# 7segement4digits1badidea-max7219-smd-mk-.net
KiCad netlist of a schematic drawn in EAGLE
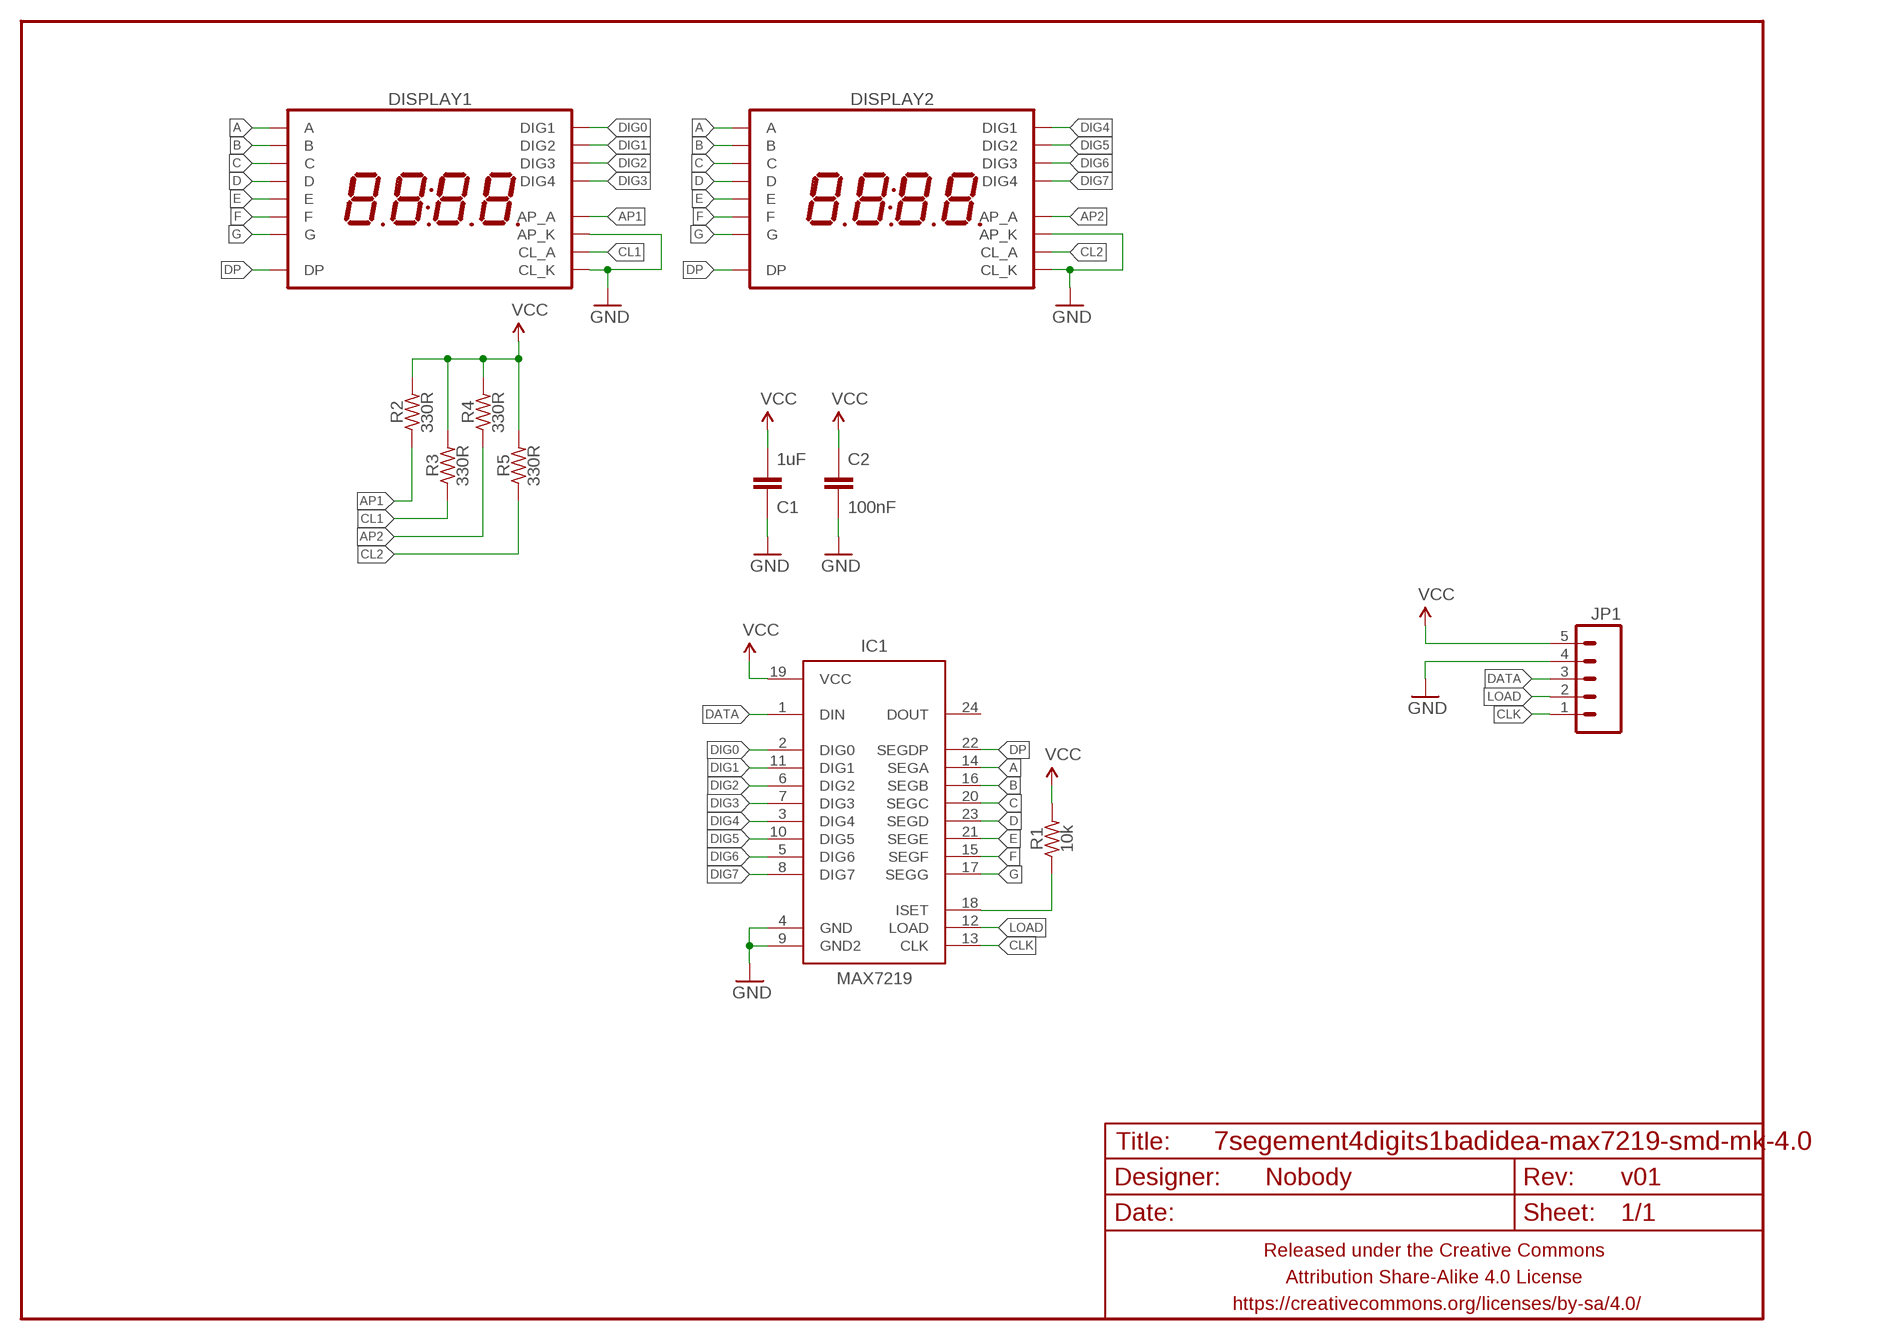
[diagram p0: schematic, sheet 1]

(export (version "E")
  (design (tool "Eeschema 10.0.6"))
  (components
    (comp (ref "C1")
      (value "1uF")
      (footprint "eagle-import:C0805")
      (libsource (lib "eagle-import") (part "CAPACITOR-CERAMICC0805"))
    )
    (comp (ref "C2")
      (value "100nF")
      (footprint "eagle-import:C0805")
      (libsource (lib "eagle-import") (part "CAPACITOR-CERAMICC0805"))
    )
    (comp (ref "DISPLAY1")
      (value "7SEG_4DIGIT_COLON_APOS")
      (footprint "eagle-import:7SEG_4DIG_10MM")
      (libsource (lib "eagle-import") (part "7SEG_4DIGIT_COLON_APOS"))
    )
    (comp (ref "DISPLAY2")
      (value "7SEG_4DIGIT_COLON_APOS")
      (footprint "eagle-import:7SEG_4DIG_10MM")
      (libsource (lib "eagle-import") (part "7SEG_4DIGIT_COLON_APOS"))
    )
    (comp (ref "FRAME1")
      (value "FRAME-LETTERNO_PACKAGE")
      (footprint "eagle-import:DUMMY")
      (fields (field (name "DESIGNER") "Nobody"))
      (libsource (lib "eagle-import") (part "FRAME-LETTERNO_PACKAGE"))
    )
    (comp (ref "IC1")
      (value "MAX7219")
      (footprint "eagle-import:SO24W")
      (libsource (lib "eagle-import") (part "MAX7219SOIC-W"))
    )
    (comp (ref "JP1")
      (value "M05PTH")
      (footprint "eagle-import:1X05")
      (libsource (lib "eagle-import") (part "M05PTH"))
    )
    (comp (ref "R1")
      (value "10k")
      (footprint "eagle-import:R0805")
      (libsource (lib "eagle-import") (part "RESISTORR0805"))
    )
    (comp (ref "R2")
      (value "330R")
      (footprint "eagle-import:R0805")
      (libsource (lib "eagle-import") (part "RESISTORR0805"))
    )
    (comp (ref "R3")
      (value "330R")
      (footprint "eagle-import:R0805")
      (libsource (lib "eagle-import") (part "RESISTORR0805"))
    )
    (comp (ref "R4")
      (value "330R")
      (footprint "eagle-import:R0805")
      (libsource (lib "eagle-import") (part "RESISTORR0805"))
    )
    (comp (ref "R5")
      (value "330R")
      (footprint "eagle-import:R0805")
      (libsource (lib "eagle-import") (part "RESISTORR0805"))
    )
  )
  (nets
    (net (code "1") (name "A") (class "Default")
      (node (ref "DISPLAY1") (pin "14") (pinfunction "A_14") (pintype "passive"))
      (node (ref "DISPLAY2") (pin "14") (pinfunction "A_14") (pintype "passive"))
      (node (ref "IC1") (pin "14") (pinfunction "SEGA_14") (pintype "bidirectional"))
    )
    (net (code "2") (name "AP1") (class "Default")
      (node (ref "DISPLAY1") (pin "10") (pinfunction "AP_A_10") (pintype "bidirectional"))
      (node (ref "R2") (pin "1") (pinfunction "1_1") (pintype "passive"))
    )
    (net (code "3") (name "AP2") (class "Default")
      (node (ref "DISPLAY2") (pin "10") (pinfunction "AP_A_10") (pintype "bidirectional"))
      (node (ref "R4") (pin "1") (pinfunction "1_1") (pintype "passive"))
    )
    (net (code "4") (name "B") (class "Default")
      (node (ref "DISPLAY1") (pin "16") (pinfunction "B_16") (pintype "passive"))
      (node (ref "DISPLAY2") (pin "16") (pinfunction "B_16") (pintype "passive"))
      (node (ref "IC1") (pin "16") (pinfunction "SEGB_16") (pintype "bidirectional"))
    )
    (net (code "5") (name "C") (class "Default")
      (node (ref "DISPLAY1") (pin "13") (pinfunction "C_13") (pintype "passive"))
      (node (ref "DISPLAY2") (pin "13") (pinfunction "C_13") (pintype "passive"))
      (node (ref "IC1") (pin "20") (pinfunction "SEGC_20") (pintype "bidirectional"))
    )
    (net (code "6") (name "CL1") (class "Default")
      (node (ref "DISPLAY1") (pin "4") (pinfunction "CL_A_4") (pintype "passive"))
      (node (ref "R3") (pin "1") (pinfunction "1_1") (pintype "passive"))
    )
    (net (code "7") (name "CL2") (class "Default")
      (node (ref "DISPLAY2") (pin "4") (pinfunction "CL_A_4") (pintype "passive"))
      (node (ref "R5") (pin "1") (pinfunction "1_1") (pintype "passive"))
    )
    (net (code "8") (name "CLK") (class "Default")
      (node (ref "IC1") (pin "13") (pinfunction "CLK_13") (pintype "bidirectional"))
      (node (ref "JP1") (pin "1") (pinfunction "1_1") (pintype "passive"))
    )
    (net (code "9") (name "D") (class "Default")
      (node (ref "DISPLAY1") (pin "3") (pinfunction "D_3") (pintype "passive"))
      (node (ref "DISPLAY2") (pin "3") (pinfunction "D_3") (pintype "passive"))
      (node (ref "IC1") (pin "23") (pinfunction "SEGD_23") (pintype "bidirectional"))
    )
    (net (code "10") (name "DATA") (class "Default")
      (node (ref "IC1") (pin "1") (pinfunction "DIN_1") (pintype "bidirectional"))
      (node (ref "JP1") (pin "3") (pinfunction "3_3") (pintype "passive"))
    )
    (net (code "11") (name "DIG0") (class "Default")
      (node (ref "DISPLAY1") (pin "1") (pinfunction "DIG1_1") (pintype "passive"))
      (node (ref "IC1") (pin "2") (pinfunction "DIG0_2") (pintype "bidirectional"))
    )
    (net (code "12") (name "DIG1") (class "Default")
      (node (ref "DISPLAY1") (pin "2") (pinfunction "DIG2_2") (pintype "passive"))
      (node (ref "IC1") (pin "11") (pinfunction "DIG1_11") (pintype "bidirectional"))
    )
    (net (code "13") (name "DIG2") (class "Default")
      (node (ref "DISPLAY1") (pin "6") (pinfunction "DIG3_6") (pintype "passive"))
      (node (ref "IC1") (pin "6") (pinfunction "DIG2_6") (pintype "bidirectional"))
    )
    (net (code "14") (name "DIG3") (class "Default")
      (node (ref "DISPLAY1") (pin "8") (pinfunction "DIG4_8") (pintype "passive"))
      (node (ref "IC1") (pin "7") (pinfunction "DIG3_7") (pintype "bidirectional"))
    )
    (net (code "15") (name "DIG4") (class "Default")
      (node (ref "DISPLAY2") (pin "1") (pinfunction "DIG1_1") (pintype "passive"))
      (node (ref "IC1") (pin "3") (pinfunction "DIG4_3") (pintype "bidirectional"))
    )
    (net (code "16") (name "DIG5") (class "Default")
      (node (ref "DISPLAY2") (pin "2") (pinfunction "DIG2_2") (pintype "passive"))
      (node (ref "IC1") (pin "10") (pinfunction "DIG5_10") (pintype "bidirectional"))
    )
    (net (code "17") (name "DIG6") (class "Default")
      (node (ref "DISPLAY2") (pin "6") (pinfunction "DIG3_6") (pintype "passive"))
      (node (ref "IC1") (pin "5") (pinfunction "DIG6_5") (pintype "bidirectional"))
    )
    (net (code "18") (name "DIG7") (class "Default")
      (node (ref "DISPLAY2") (pin "8") (pinfunction "DIG4_8") (pintype "passive"))
      (node (ref "IC1") (pin "8") (pinfunction "DIG7_8") (pintype "bidirectional"))
    )
    (net (code "19") (name "DP") (class "Default")
      (node (ref "DISPLAY1") (pin "7") (pinfunction "DP_7") (pintype "passive"))
      (node (ref "DISPLAY2") (pin "7") (pinfunction "DP_7") (pintype "passive"))
      (node (ref "IC1") (pin "22") (pinfunction "SEGDP_22") (pintype "bidirectional"))
    )
    (net (code "20") (name "E") (class "Default")
      (node (ref "DISPLAY1") (pin "5") (pinfunction "E_5") (pintype "passive"))
      (node (ref "DISPLAY2") (pin "5") (pinfunction "E_5") (pintype "passive"))
      (node (ref "IC1") (pin "21") (pinfunction "SEGE_21") (pintype "bidirectional"))
    )
    (net (code "21") (name "F") (class "Default")
      (node (ref "DISPLAY1") (pin "11") (pinfunction "F_11") (pintype "passive"))
      (node (ref "DISPLAY2") (pin "11") (pinfunction "F_11") (pintype "passive"))
      (node (ref "IC1") (pin "15") (pinfunction "SEGF_15") (pintype "bidirectional"))
    )
    (net (code "22") (name "G") (class "Default")
      (node (ref "DISPLAY1") (pin "15") (pinfunction "G_15") (pintype "passive"))
      (node (ref "DISPLAY2") (pin "15") (pinfunction "G_15") (pintype "passive"))
      (node (ref "IC1") (pin "17") (pinfunction "SEGG_17") (pintype "bidirectional"))
    )
    (net (code "23") (name "GND") (class "Default")
      (node (ref "C1") (pin "1") (pinfunction "1_1") (pintype "passive"))
      (node (ref "C2") (pin "2") (pinfunction "2_2") (pintype "passive"))
      (node (ref "DISPLAY1") (pin "12") (pinfunction "CL_K_12") (pintype "passive"))
      (node (ref "DISPLAY1") (pin "9") (pinfunction "AP_K_9") (pintype "bidirectional"))
      (node (ref "DISPLAY2") (pin "12") (pinfunction "CL_K_12") (pintype "passive"))
      (node (ref "DISPLAY2") (pin "9") (pinfunction "AP_K_9") (pintype "bidirectional"))
      (node (ref "IC1") (pin "4") (pinfunction "GND_4") (pintype "bidirectional"))
      (node (ref "IC1") (pin "9") (pinfunction "GND2_9") (pintype "bidirectional"))
      (node (ref "JP1") (pin "4") (pinfunction "4_4") (pintype "passive"))
    )
    (net (code "24") (name "LOAD") (class "Default")
      (node (ref "IC1") (pin "12") (pinfunction "LOAD_12") (pintype "bidirectional"))
      (node (ref "JP1") (pin "2") (pinfunction "2_2") (pintype "passive"))
    )
    (net (code "25") (name "Net-(IC1-ISET)") (class "Default")
      (node (ref "IC1") (pin "18") (pinfunction "ISET_18") (pintype "bidirectional"))
      (node (ref "R1") (pin "1") (pinfunction "1_1") (pintype "passive"))
    )
    (net (code "26") (name "VCC") (class "Default")
      (node (ref "C1") (pin "2") (pinfunction "2_2") (pintype "passive"))
      (node (ref "C2") (pin "1") (pinfunction "1_1") (pintype "passive"))
      (node (ref "IC1") (pin "19") (pinfunction "VCC_19") (pintype "bidirectional"))
      (node (ref "JP1") (pin "5") (pinfunction "5_5") (pintype "passive"))
      (node (ref "R1") (pin "2") (pinfunction "2_2") (pintype "passive"))
      (node (ref "R2") (pin "2") (pinfunction "2_2") (pintype "passive"))
      (node (ref "R3") (pin "2") (pinfunction "2_2") (pintype "passive"))
      (node (ref "R4") (pin "2") (pinfunction "2_2") (pintype "passive"))
      (node (ref "R5") (pin "2") (pinfunction "2_2") (pintype "passive"))
    )
    (net (code "27") (name "unconnected-(IC1-DOUT-Pad24)") (class "Default")
      (node (ref "IC1") (pin "24") (pinfunction "DOUT_24") (pintype "bidirectional"))
    )
  )
)
